# untitled.net
KiCad netlist of a schematic drawn in EAGLE
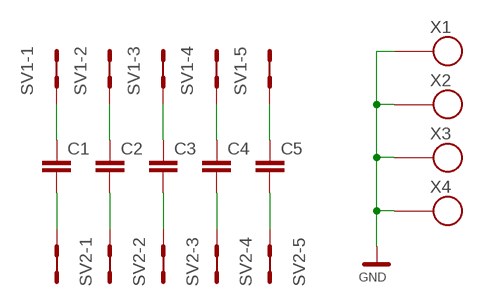
[diagram p0: schematic, sheet 1]

(export (version "E")
  (design (tool "Eeschema 10.0.6"))
  (components
    (comp (ref "C1")
      (value "C0805")
      (footprint "eagle-import:C0805")
      (libsource (lib "eagle-import") (part "C0805"))
    )
    (comp (ref "C2")
      (value "C0805")
      (footprint "eagle-import:C0805")
      (libsource (lib "eagle-import") (part "C0805"))
    )
    (comp (ref "C3")
      (value "C0805")
      (footprint "eagle-import:C0805")
      (libsource (lib "eagle-import") (part "C0805"))
    )
    (comp (ref "C4")
      (value "C0805")
      (footprint "eagle-import:C0805")
      (libsource (lib "eagle-import") (part "C0805"))
    )
    (comp (ref "C5")
      (value "C0805")
      (footprint "eagle-import:C0805")
      (libsource (lib "eagle-import") (part "C0805"))
    )
    (comp (ref "SV1")
      (value "MA05-2")
      (footprint "eagle-import:MA05-2")
      (libsource (lib "eagle-import") (part "MA05-2"))
    )
    (comp (ref "SV2")
      (value "MA05-2")
      (footprint "eagle-import:MA05-2")
      (libsource (lib "eagle-import") (part "MA05-2"))
    )
    (comp (ref "X1")
      (value "SROUB3M")
      (footprint "eagle-import:SROUB3M")
      (libsource (lib "eagle-import") (part "SROUB3M"))
    )
    (comp (ref "X2")
      (value "SROUB3M")
      (footprint "eagle-import:SROUB3M")
      (libsource (lib "eagle-import") (part "SROUB3M"))
    )
    (comp (ref "X3")
      (value "SROUB3M")
      (footprint "eagle-import:SROUB3M")
      (libsource (lib "eagle-import") (part "SROUB3M"))
    )
    (comp (ref "X4")
      (value "SROUB3M")
      (footprint "eagle-import:SROUB3M")
      (libsource (lib "eagle-import") (part "SROUB3M"))
    )
  )
  (nets
    (net (code "1") (name "GND") (class "Default")
      (node (ref "X1") (pin "P$1") (pinfunction "P$1_P$1") (pintype "bidirectional"))
      (node (ref "X2") (pin "P$1") (pinfunction "P$1_P$1") (pintype "bidirectional"))
      (node (ref "X3") (pin "P$1") (pinfunction "P$1_P$1") (pintype "bidirectional"))
      (node (ref "X4") (pin "P$1") (pinfunction "P$1_P$1") (pintype "bidirectional"))
    )
    (net (code "2") (name "Net-(C1-Pad1)") (class "Default")
      (node (ref "C1") (pin "1") (pinfunction "1_1") (pintype "passive"))
      (node (ref "SV1") (pin "1") (pinfunction "K_1") (pintype "passive"))
      (node (ref "SV1") (pin "2") (pinfunction "K_2") (pintype "passive"))
    )
    (net (code "3") (name "Net-(C1-Pad2)") (class "Default")
      (node (ref "C1") (pin "2") (pinfunction "2_2") (pintype "passive"))
      (node (ref "SV2") (pin "1") (pinfunction "K_1") (pintype "passive"))
      (node (ref "SV2") (pin "2") (pinfunction "K_2") (pintype "passive"))
    )
    (net (code "4") (name "Net-(C2-Pad1)") (class "Default")
      (node (ref "C2") (pin "1") (pinfunction "1_1") (pintype "passive"))
      (node (ref "SV1") (pin "3") (pinfunction "K_3") (pintype "passive"))
      (node (ref "SV1") (pin "4") (pinfunction "K_4") (pintype "passive"))
    )
    (net (code "5") (name "Net-(C2-Pad2)") (class "Default")
      (node (ref "C2") (pin "2") (pinfunction "2_2") (pintype "passive"))
      (node (ref "SV2") (pin "3") (pinfunction "K_3") (pintype "passive"))
      (node (ref "SV2") (pin "4") (pinfunction "K_4") (pintype "passive"))
    )
    (net (code "6") (name "Net-(C3-Pad1)") (class "Default")
      (node (ref "C3") (pin "1") (pinfunction "1_1") (pintype "passive"))
      (node (ref "SV1") (pin "5") (pinfunction "K_5") (pintype "passive"))
      (node (ref "SV1") (pin "6") (pinfunction "K_6") (pintype "passive"))
    )
    (net (code "7") (name "Net-(C3-Pad2)") (class "Default")
      (node (ref "C3") (pin "2") (pinfunction "2_2") (pintype "passive"))
      (node (ref "SV2") (pin "5") (pinfunction "K_5") (pintype "passive"))
      (node (ref "SV2") (pin "6") (pinfunction "K_6") (pintype "passive"))
    )
    (net (code "8") (name "Net-(C4-Pad1)") (class "Default")
      (node (ref "C4") (pin "1") (pinfunction "1_1") (pintype "passive"))
      (node (ref "SV1") (pin "7") (pinfunction "K_7") (pintype "passive"))
      (node (ref "SV1") (pin "8") (pinfunction "K_8") (pintype "passive"))
    )
    (net (code "9") (name "Net-(C4-Pad2)") (class "Default")
      (node (ref "C4") (pin "2") (pinfunction "2_2") (pintype "passive"))
      (node (ref "SV2") (pin "7") (pinfunction "K_7") (pintype "passive"))
      (node (ref "SV2") (pin "8") (pinfunction "K_8") (pintype "passive"))
    )
    (net (code "10") (name "Net-(C5-Pad1)") (class "Default")
      (node (ref "C5") (pin "1") (pinfunction "1_1") (pintype "passive"))
      (node (ref "SV1") (pin "10") (pinfunction "K_10") (pintype "passive"))
      (node (ref "SV1") (pin "9") (pinfunction "K_9") (pintype "passive"))
    )
    (net (code "11") (name "Net-(C5-Pad2)") (class "Default")
      (node (ref "C5") (pin "2") (pinfunction "2_2") (pintype "passive"))
      (node (ref "SV2") (pin "10") (pinfunction "K_10") (pintype "passive"))
      (node (ref "SV2") (pin "9") (pinfunction "K_9") (pintype "passive"))
    )
  )
)
